# BabyPad.net
KiCad netlist of a schematic drawn in EAGLE
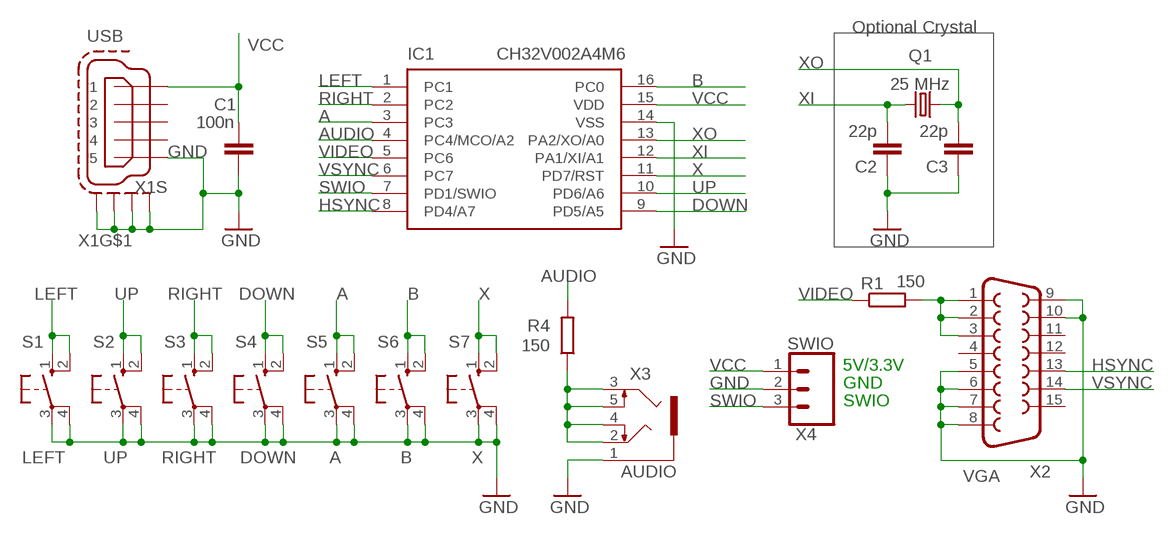
[diagram p0: schematic, sheet 1]

(export (version "E")
  (design (tool "Eeschema 10.0.6"))
  (components
    (comp (ref "C1")
      (value "100n")
      (footprint "eagle-import:C050-024X044")
      (libsource (lib "eagle-import") (part "C-EU050-024X044"))
    )
    (comp (ref "C2")
      (value "22p")
      (footprint "eagle-import:C050-024X044")
      (libsource (lib "eagle-import") (part "C-EU050-024X044"))
    )
    (comp (ref "C3")
      (value "22p")
      (footprint "eagle-import:C050-024X044")
      (libsource (lib "eagle-import") (part "C-EU050-024X044"))
    )
    (comp (ref "IC1")
      (value "CH32V002A4M6")
      (footprint "eagle-import:SOP16")
      (libsource (lib "eagle-import") (part "CH32V002A4M6"))
    )
    (comp (ref "Q1")
      (value "25 MHz")
      (footprint "eagle-import:HC49U-V")
      (libsource (lib "eagle-import") (part "CRYSTALHC49U-V"))
    )
    (comp (ref "R1")
      (value "150")
      (footprint "eagle-import:0204_7")
      (libsource (lib "eagle-import") (part "R-EU_0204/7"))
    )
    (comp (ref "R4")
      (value "150")
      (footprint "eagle-import:0204_7")
      (libsource (lib "eagle-import") (part "R-EU_0204/7"))
    )
    (comp (ref "S1")
      (value "LEFT")
      (footprint "eagle-import:B3F-10XX")
      (fields (field (name "MPN") "B3F-1000"))
      (libsource (lib "eagle-import") (part "10-XX"))
    )
    (comp (ref "S2")
      (value "UP")
      (footprint "eagle-import:B3F-10XX")
      (fields (field (name "MPN") "B3F-1000"))
      (libsource (lib "eagle-import") (part "10-XX"))
    )
    (comp (ref "S3")
      (value "RIGHT")
      (footprint "eagle-import:B3F-10XX")
      (fields (field (name "MPN") "B3F-1000"))
      (libsource (lib "eagle-import") (part "10-XX"))
    )
    (comp (ref "S4")
      (value "DOWN")
      (footprint "eagle-import:B3F-10XX")
      (fields (field (name "MPN") "B3F-1000"))
      (libsource (lib "eagle-import") (part "10-XX"))
    )
    (comp (ref "S5")
      (value "A")
      (footprint "eagle-import:B3F-10XX")
      (fields (field (name "MPN") "B3F-1000"))
      (libsource (lib "eagle-import") (part "10-XX"))
    )
    (comp (ref "S6")
      (value "B")
      (footprint "eagle-import:B3F-10XX")
      (fields (field (name "MPN") "B3F-1000"))
      (libsource (lib "eagle-import") (part "10-XX"))
    )
    (comp (ref "S7")
      (value "X")
      (footprint "eagle-import:B3F-10XX")
      (fields (field (name "MPN") "B3F-1000"))
      (libsource (lib "eagle-import") (part "10-XX"))
    )
    (comp (ref "X1")
      (value "USB")
      (footprint "eagle-import:32005-201")
      (libsource (lib "eagle-import") (part "MINI-USB-SCHIELD-32005-201"))
    )
    (comp (ref "X2")
      (value "VGA")
      (footprint "eagle-import:HDF15H")
      (libsource (lib "eagle-import") (part "F15HDH"))
    )
    (comp (ref "X3")
      (value "AUDIO")
      (footprint "eagle-import:1503_09")
      (libsource (lib "eagle-import") (part "1503_09"))
    )
    (comp (ref "X4")
      (value "SWIO")
      (footprint "eagle-import:1X03_LONGPADS")
      (libsource (lib "eagle-import") (part "CONN_03LONGPADS"))
    )
  )
  (nets
    (net (code "1") (name "/A") (class "Default")
      (node (ref "IC1") (pin "3") (pinfunction "PC3_3") (pintype "bidirectional"))
      (node (ref "S5") (pin "1") (pinfunction "S_1") (pintype "passive"))
      (node (ref "S5") (pin "2") (pinfunction "S1_2") (pintype "passive"))
    )
    (net (code "2") (name "/AUDIO") (class "Default")
      (node (ref "IC1") (pin "4") (pinfunction "PC4/MCO/A2_4") (pintype "bidirectional"))
      (node (ref "R4") (pin "2") (pinfunction "2_2") (pintype "passive"))
    )
    (net (code "3") (name "/B") (class "Default")
      (node (ref "IC1") (pin "16") (pinfunction "PC0_16") (pintype "bidirectional"))
      (node (ref "S6") (pin "1") (pinfunction "S_1") (pintype "passive"))
      (node (ref "S6") (pin "2") (pinfunction "S1_2") (pintype "passive"))
    )
    (net (code "4") (name "/DOWN") (class "Default")
      (node (ref "IC1") (pin "9") (pinfunction "PD5/A5_9") (pintype "bidirectional"))
      (node (ref "S4") (pin "1") (pinfunction "S_1") (pintype "passive"))
      (node (ref "S4") (pin "2") (pinfunction "S1_2") (pintype "passive"))
    )
    (net (code "5") (name "/HSYNC") (class "Default")
      (node (ref "IC1") (pin "8") (pinfunction "PD4/A7_8") (pintype "bidirectional"))
      (node (ref "X2") (pin "13") (pinfunction "13_13") (pintype "passive"))
    )
    (net (code "6") (name "/LEFT") (class "Default")
      (node (ref "IC1") (pin "1") (pinfunction "PC1_1") (pintype "bidirectional"))
      (node (ref "S1") (pin "1") (pinfunction "S_1") (pintype "passive"))
      (node (ref "S1") (pin "2") (pinfunction "S1_2") (pintype "passive"))
    )
    (net (code "7") (name "/RIGHT") (class "Default")
      (node (ref "IC1") (pin "2") (pinfunction "PC2_2") (pintype "bidirectional"))
      (node (ref "S3") (pin "1") (pinfunction "S_1") (pintype "passive"))
      (node (ref "S3") (pin "2") (pinfunction "S1_2") (pintype "passive"))
    )
    (net (code "8") (name "/SWIO") (class "Default")
      (node (ref "IC1") (pin "7") (pinfunction "PD1/SWIO_7") (pintype "bidirectional"))
      (node (ref "X4") (pin "3") (pinfunction "3_3") (pintype "passive"))
    )
    (net (code "9") (name "/UP") (class "Default")
      (node (ref "IC1") (pin "10") (pinfunction "PD6/A6_10") (pintype "bidirectional"))
      (node (ref "S2") (pin "1") (pinfunction "S_1") (pintype "passive"))
      (node (ref "S2") (pin "2") (pinfunction "S1_2") (pintype "passive"))
    )
    (net (code "10") (name "/VCC") (class "Default")
      (node (ref "C1") (pin "1") (pinfunction "1_1") (pintype "passive"))
      (node (ref "IC1") (pin "15") (pinfunction "VDD_15") (pintype "power_in"))
      (node (ref "X1") (pin "1") (pinfunction "1_1") (pintype "passive"))
      (node (ref "X4") (pin "1") (pinfunction "1_1") (pintype "passive"))
    )
    (net (code "11") (name "/VIDEO") (class "Default")
      (node (ref "IC1") (pin "5") (pinfunction "PC6_5") (pintype "bidirectional"))
      (node (ref "R1") (pin "1") (pinfunction "1_1") (pintype "passive"))
    )
    (net (code "12") (name "/VSYNC") (class "Default")
      (node (ref "IC1") (pin "6") (pinfunction "PC7_6") (pintype "bidirectional"))
      (node (ref "X2") (pin "14") (pinfunction "14_14") (pintype "passive"))
    )
    (net (code "13") (name "/X") (class "Default")
      (node (ref "IC1") (pin "11") (pinfunction "PD7/RST_11") (pintype "bidirectional"))
      (node (ref "S7") (pin "1") (pinfunction "S_1") (pintype "passive"))
      (node (ref "S7") (pin "2") (pinfunction "S1_2") (pintype "passive"))
    )
    (net (code "14") (name "/XI") (class "Default")
      (node (ref "C2") (pin "2") (pinfunction "2_2") (pintype "passive"))
      (node (ref "IC1") (pin "12") (pinfunction "PA1/XI/A1_12") (pintype "bidirectional"))
      (node (ref "Q1") (pin "2") (pinfunction "2_2") (pintype "passive"))
    )
    (net (code "15") (name "/XO") (class "Default")
      (node (ref "C3") (pin "2") (pinfunction "2_2") (pintype "passive"))
      (node (ref "IC1") (pin "13") (pinfunction "PA2/XO/A0_13") (pintype "bidirectional"))
      (node (ref "Q1") (pin "1") (pinfunction "1_1") (pintype "passive"))
    )
    (net (code "16") (name "GND") (class "Default")
      (node (ref "C1") (pin "2") (pinfunction "2_2") (pintype "passive"))
      (node (ref "C2") (pin "1") (pinfunction "1_1") (pintype "passive"))
      (node (ref "C3") (pin "1") (pinfunction "1_1") (pintype "passive"))
      (node (ref "IC1") (pin "14") (pinfunction "VSS_14") (pintype "power_in"))
      (node (ref "S1") (pin "3") (pinfunction "P_3") (pintype "passive"))
      (node (ref "S1") (pin "4") (pinfunction "P1_4") (pintype "passive"))
      (node (ref "S2") (pin "3") (pinfunction "P_3") (pintype "passive"))
      (node (ref "S2") (pin "4") (pinfunction "P1_4") (pintype "passive"))
      (node (ref "S3") (pin "3") (pinfunction "P_3") (pintype "passive"))
      (node (ref "S3") (pin "4") (pinfunction "P1_4") (pintype "passive"))
      (node (ref "S4") (pin "3") (pinfunction "P_3") (pintype "passive"))
      (node (ref "S4") (pin "4") (pinfunction "P1_4") (pintype "passive"))
      (node (ref "S5") (pin "3") (pinfunction "P_3") (pintype "passive"))
      (node (ref "S5") (pin "4") (pinfunction "P1_4") (pintype "passive"))
      (node (ref "S6") (pin "3") (pinfunction "P_3") (pintype "passive"))
      (node (ref "S6") (pin "4") (pinfunction "P1_4") (pintype "passive"))
      (node (ref "S7") (pin "3") (pinfunction "P_3") (pintype "passive"))
      (node (ref "S7") (pin "4") (pinfunction "P1_4") (pintype "passive"))
      (node (ref "X1") (pin "5") (pinfunction "5_5") (pintype "passive"))
      (node (ref "X1") (pin "M1") (pinfunction "S1_M1") (pintype "passive"))
      (node (ref "X1") (pin "M2") (pinfunction "S2_M2") (pintype "passive"))
      (node (ref "X1") (pin "M3") (pinfunction "S3_M3") (pintype "passive"))
      (node (ref "X1") (pin "M4") (pinfunction "S4_M4") (pintype "passive"))
      (node (ref "X2") (pin "10") (pinfunction "10_10") (pintype "passive"))
      (node (ref "X2") (pin "5") (pinfunction "5_5") (pintype "passive"))
      (node (ref "X2") (pin "6") (pinfunction "6_6") (pintype "passive"))
      (node (ref "X2") (pin "7") (pinfunction "7_7") (pintype "passive"))
      (node (ref "X2") (pin "8") (pinfunction "8_8") (pintype "passive"))
      (node (ref "X2") (pin "9") (pinfunction "9_9") (pintype "passive"))
      (node (ref "X3") (pin "1") (pinfunction "1_1") (pintype "passive"))
      (node (ref "X4") (pin "2") (pinfunction "2_2") (pintype "passive"))
    )
    (net (code "17") (name "Net-(R1-Pad2)") (class "Default")
      (node (ref "R1") (pin "2") (pinfunction "2_2") (pintype "passive"))
      (node (ref "X2") (pin "1") (pinfunction "1_1") (pintype "passive"))
      (node (ref "X2") (pin "2") (pinfunction "2_2") (pintype "passive"))
      (node (ref "X2") (pin "3") (pinfunction "3_3") (pintype "passive"))
    )
    (net (code "18") (name "Net-(R4-Pad1)") (class "Default")
      (node (ref "R4") (pin "1") (pinfunction "1_1") (pintype "passive"))
      (node (ref "X3") (pin "2") (pinfunction "2_2") (pintype "passive"))
      (node (ref "X3") (pin "3") (pinfunction "3_3") (pintype "passive"))
      (node (ref "X3") (pin "4") (pinfunction "4_4") (pintype "passive"))
      (node (ref "X3") (pin "5") (pinfunction "5_5") (pintype "passive"))
    )
    (net (code "19") (name "unconnected-(X1-Pad2)") (class "Default")
      (node (ref "X1") (pin "2") (pinfunction "2_2") (pintype "passive"))
    )
    (net (code "20") (name "unconnected-(X1-Pad3)") (class "Default")
      (node (ref "X1") (pin "3") (pinfunction "3_3") (pintype "passive"))
    )
    (net (code "21") (name "unconnected-(X1-Pad4)") (class "Default")
      (node (ref "X1") (pin "4") (pinfunction "4_4") (pintype "passive"))
    )
    (net (code "22") (name "unconnected-(X2-Pad4)") (class "Default")
      (node (ref "X2") (pin "4") (pinfunction "4_4") (pintype "passive"))
    )
    (net (code "23") (name "unconnected-(X2-Pad11)") (class "Default")
      (node (ref "X2") (pin "11") (pinfunction "11_11") (pintype "passive"))
    )
    (net (code "24") (name "unconnected-(X2-Pad12)") (class "Default")
      (node (ref "X2") (pin "12") (pinfunction "12_12") (pintype "passive"))
    )
    (net (code "25") (name "unconnected-(X2-Pad15)") (class "Default")
      (node (ref "X2") (pin "15") (pinfunction "15_15") (pintype "passive"))
    )
  )
)
